# Sheet1.net
KiCad netlist of a schematic drawn in Altium Designer
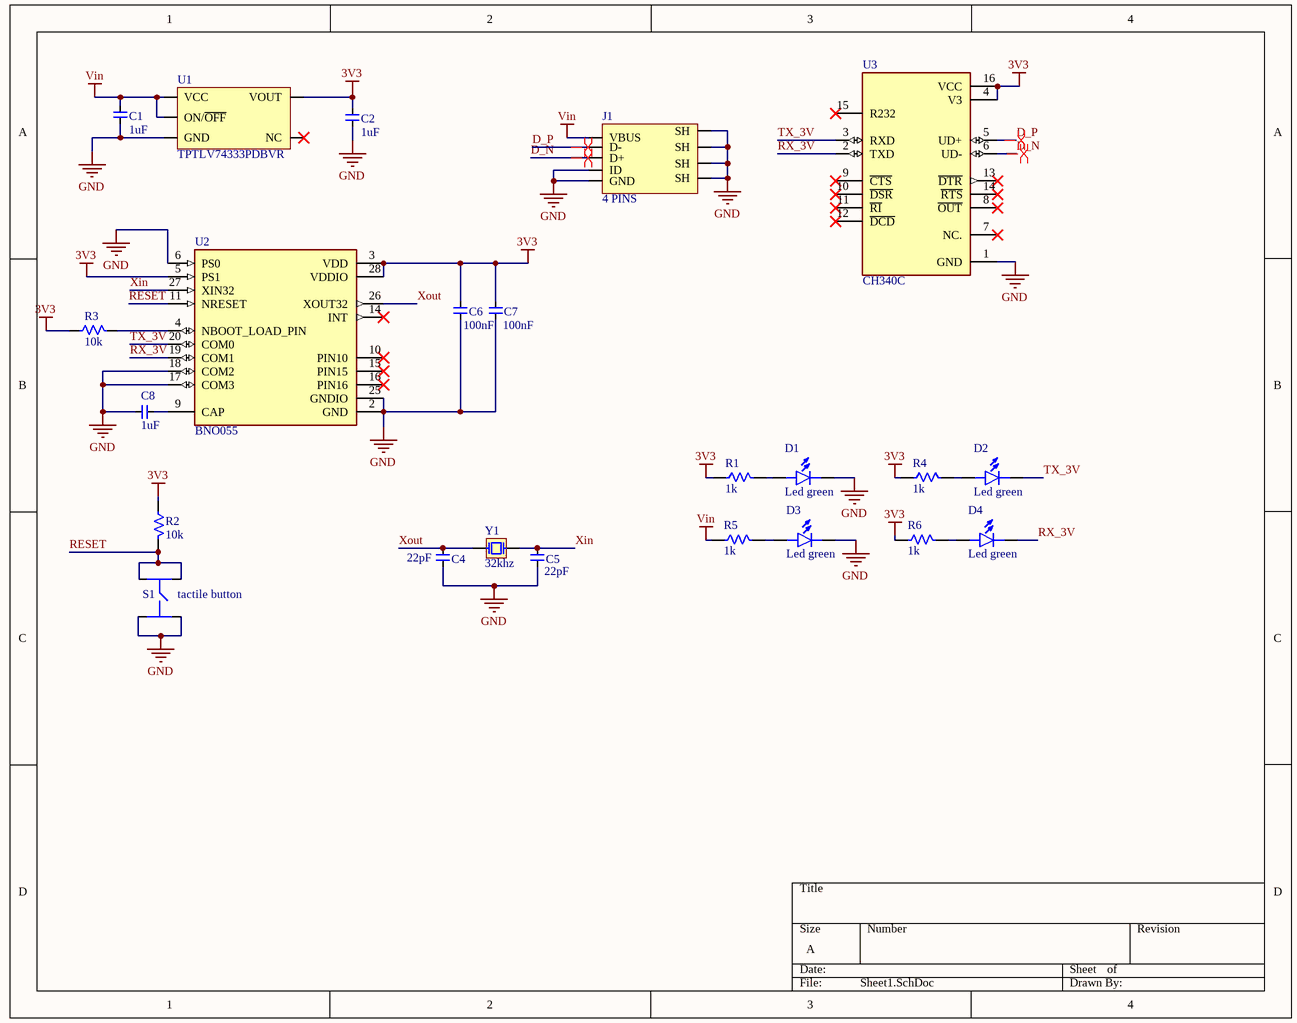
[diagram p0: Sheet1.SchDoc]

(export (version "E")
  (design (tool "Eeschema 10.0.6"))
  (components
    (comp (ref "C1")
      (value "1uF")
      (footprint "0603 cap")
      (description "25V 1uF X7R ±10% 0603 Multilayer Ceramic Capacitors MLCC - SMD/SMT ROHS")
      (fields
        (field (name "MANUFACTURER") "PSA(Prosperity Dielectrics)")
        (field (name "MFR. PART #") "FS18X105K250PBG")
      )
      (libsource (lib "Schlib1") (part "1uF"))
    )
    (comp (ref "C2")
      (value "1uF")
      (footprint "0603 cap")
      (description "25V 1uF X7R ±10% 0603 Multilayer Ceramic Capacitors MLCC - SMD/SMT ROHS")
      (fields
        (field (name "MANUFACTURER") "PSA(Prosperity Dielectrics)")
        (field (name "MFR. PART #") "FS18X105K250PBG")
      )
      (libsource (lib "Schlib1") (part "1uF"))
    )
    (comp (ref "C4")
      (value "22pF")
      (footprint "0603 cap")
      (description "50V 22pF C0G ±5% 0603 Multilayer Ceramic Capacitors MLCC - SMD/SMT ROHS")
      (fields
        (field (name "MANUFACTURER") "PSA(Prosperity Dielectrics)")
        (field (name "MFR. PART #") "FN18N220J500PSG")
      )
      (libsource (lib "Schlib1") (part "22pF capacitor"))
    )
    (comp (ref "C5")
      (value "22pF")
      (footprint "0603 cap")
      (description "50V 22pF C0G ±5% 0603 Multilayer Ceramic Capacitors MLCC - SMD/SMT ROHS")
      (fields
        (field (name "MANUFACTURER") "PSA(Prosperity Dielectrics)")
        (field (name "MFR. PART #") "FN18N220J500PSG")
      )
      (libsource (lib "Schlib1") (part "22pF capacitor"))
    )
    (comp (ref "C6")
      (value "100nF")
      (footprint "0603 cap")
      (description "50V 100nF X7R ±10% 0603 Multilayer Ceramic Capacitors MLCC - SMD/SMT ROHS")
      (fields
        (field (name "MANUFACTURER") "PSA(Prosperity Dielectrics)")
        (field (name "MFR. PART #") "FN18X104K500PBG")
      )
      (libsource (lib "Schlib1") (part "100nF capacitor"))
    )
    (comp (ref "C7")
      (value "100nF")
      (footprint "0603 cap")
      (description "50V 100nF X7R ±10% 0603 Multilayer Ceramic Capacitors MLCC - SMD/SMT ROHS")
      (fields
        (field (name "MANUFACTURER") "PSA(Prosperity Dielectrics)")
        (field (name "MFR. PART #") "FN18X104K500PBG")
      )
      (libsource (lib "Schlib1") (part "100nF capacitor"))
    )
    (comp (ref "C8")
      (value "1uF")
      (footprint "0603 cap")
      (description "25V 1uF X7R ±10% 0603 Multilayer Ceramic Capacitors MLCC - SMD/SMT ROHS")
      (fields
        (field (name "MANUFACTURER") "PSA(Prosperity Dielectrics)")
        (field (name "MFR. PART #") "FS18X105K250PBG")
      )
      (libsource (lib "Schlib1") (part "1uF"))
    )
    (comp (ref "D1")
      (value "Led green")
      (footprint "0805led")
      (description "Emerald 0805 Light Emitting Diodes (LED) ROHS")
      (fields (field (name "MANUFACTURER") "Yongyu Photoelectric") (field (name "MFR. PART #") "SZYY0805G"))
      (libsource (lib "Schlib1") (part "Led green"))
    )
    (comp (ref "D2")
      (value "Led green")
      (footprint "0805led")
      (description "Emerald 0805 Light Emitting Diodes (LED) ROHS")
      (fields (field (name "MANUFACTURER") "Yongyu Photoelectric") (field (name "MFR. PART #") "SZYY0805G"))
      (libsource (lib "Schlib1") (part "Led green"))
    )
    (comp (ref "D3")
      (value "Led green")
      (footprint "0805led")
      (description "Emerald 0805 Light Emitting Diodes (LED) ROHS")
      (fields (field (name "MANUFACTURER") "Yongyu Photoelectric") (field (name "MFR. PART #") "SZYY0805G"))
      (libsource (lib "Schlib1") (part "Led green"))
    )
    (comp (ref "D4")
      (value "Led green")
      (footprint "0805led")
      (description "Emerald 0805 Light Emitting Diodes (LED) ROHS")
      (fields (field (name "MANUFACTURER") "Yongyu Photoelectric") (field (name "MFR. PART #") "SZYY0805G"))
      (libsource (lib "Schlib1") (part "Led green"))
    )
    (comp (ref "J1")
      (value "4 PINS")
      (footprint "Micro USB")
      (description "1.8A USB 2.0 1 Horizontal attachment 5P Mother -20℃~+85℃ Micro-B SMD USB Connectors ROHS")
      (fields (field (name "MANUFACTURER") "SHOU HAN") (field (name "MFR. PART #") "MicroXNJ"))
      (libsource (lib "Schlib1") (part "Micro USB"))
    )
    (comp (ref "R1")
      (value "1k")
      (footprint "0603 res")
      (description "100mW Thick Film Resistors 75V ±100ppm/℃ ±1% 1kΩ 0603 Chip Resistor - Surface Mount ROHS")
      (fields
        (field (name "MANUFACTURER") "UNI-ROYAL(Uniroyal Elec)")
        (field (name "MFR. PART #") "0603WAF1001T5E")
      )
      (libsource (lib "Schlib1") (part "1k resistor"))
    )
    (comp (ref "R2")
      (value "10k")
      (footprint "0603 res")
      (description "100mW Thick Film Resistors 75V ±100ppm/℃ ±1% 10kΩ 0603 Chip Resistor - Surface Mount ROHS")
      (fields
        (field (name "MANUFACTURER") "UNI-ROYAL(Uniroyal Elec)")
        (field (name "MFR. PART #") "0603WAF1002T5E")
      )
      (libsource (lib "Schlib1") (part "10k resistor"))
    )
    (comp (ref "R3")
      (value "10k")
      (footprint "0603 res")
      (description "100mW Thick Film Resistors 75V ±100ppm/℃ ±1% 10kΩ 0603 Chip Resistor - Surface Mount ROHS")
      (fields
        (field (name "MANUFACTURER") "UNI-ROYAL(Uniroyal Elec)")
        (field (name "MFR. PART #") "0603WAF1002T5E")
      )
      (libsource (lib "Schlib1") (part "10k resistor"))
    )
    (comp (ref "R4")
      (value "1k")
      (footprint "0603 res")
      (description "100mW Thick Film Resistors 75V ±100ppm/℃ ±1% 1kΩ 0603 Chip Resistor - Surface Mount ROHS")
      (fields
        (field (name "MANUFACTURER") "UNI-ROYAL(Uniroyal Elec)")
        (field (name "MFR. PART #") "0603WAF1001T5E")
      )
      (libsource (lib "Schlib1") (part "1k resistor"))
    )
    (comp (ref "R5")
      (value "1k")
      (footprint "0603 res")
      (description "100mW Thick Film Resistors 75V ±100ppm/℃ ±1% 1kΩ 0603 Chip Resistor - Surface Mount ROHS")
      (fields
        (field (name "MANUFACTURER") "UNI-ROYAL(Uniroyal Elec)")
        (field (name "MFR. PART #") "0603WAF1001T5E")
      )
      (libsource (lib "Schlib1") (part "1k resistor"))
    )
    (comp (ref "R6")
      (value "1k")
      (footprint "0603 res")
      (description "100mW Thick Film Resistors 75V ±100ppm/℃ ±1% 1kΩ 0603 Chip Resistor - Surface Mount ROHS")
      (fields
        (field (name "MANUFACTURER") "UNI-ROYAL(Uniroyal Elec)")
        (field (name "MFR. PART #") "0603WAF1001T5E")
      )
      (libsource (lib "Schlib1") (part "1k resistor"))
    )
    (comp (ref "S1")
      (value "tactile button")
      (footprint "button")
      (fields
        (field (name "MANUFACTURER") "XKB Connection")
        (field (name "MFR. PART #") "UK-B0240-R-250")
        (field (name "LCSC PART #") "C318884")
      )
      (libsource (lib "Schlib1") (part "Button"))
    )
    (comp (ref "U1")
      (value "TPTLV74333PDBVR")
      (footprint "SOT-23")
      (fields (field (name "MANUFACTURER") "TECH PUBLIC") (field (name "LCSC PART #") "C3021096"))
      (libsource (lib "Schlib1") (part "TPTLV74333PDBVR"))
    )
    (comp (ref "U2")
      (value "BNO055")
      (footprint "LGA28R50P4X10_380X520X100")
      (description "LGA-28(3.8x5.2) Accelerometers ROHS")
      (fields (field (name "MANUFACTURER") "Bosch Sensortec") (field (name "LCSC PART #") "C93216"))
      (libsource (lib "Schlib1") (part "BNO055"))
    )
    (comp (ref "U3")
      (value "CH340C")
      (footprint "sop 16")
      (description "2Mbps Transceiver USB 2.0 SOP-16 USB ICs ROHS")
      (fields (field (name "MANUFACTURER") "WCH") (field (name "LCSC PART #") "C84681"))
      (libsource (lib "Schlib1") (part "CH340C"))
    )
    (comp (ref "Y1")
      (value "32khz")
      (footprint "XTAL_ABS06-107-32.768KHZ-T")
      (description "32.768kHz 6pF ±10ppm SMD2012-2P Crystals ROHS")
      (fields
        (field (name "MANUFACTURER") "Abracon LLC")
        (field (name "MFR. PART #") "ABS06-32.768KHZ-6-1-T")
      )
      (libsource (lib "Schlib1") (part "32khz"))
    )
  )
  (nets
    (net (code "1") (name "/D_N") (class "Default")
      (node (ref "J1") (pin "3") (pinfunction "D+_3") (pintype "passive"))
      (node (ref "U3") (pin "6") (pinfunction "UD-_6") (pintype "bidirectional"))
    )
    (net (code "2") (name "/D_P") (class "Default")
      (node (ref "J1") (pin "2") (pinfunction "D-_2") (pintype "passive"))
      (node (ref "U3") (pin "5") (pinfunction "UD+_5") (pintype "bidirectional"))
    )
    (net (code "3") (name "/RESET") (class "Default")
      (node (ref "R2") (pin "2") (pinfunction "2_2") (pintype "passive"))
      (node (ref "S1") (pin "C") (pinfunction "C_C") (pintype "passive"))
      (node (ref "S1") (pin "D") (pinfunction "D_D") (pintype "passive"))
      (node (ref "U2") (pin "11") (pinfunction "NRESET_11") (pintype "input"))
    )
    (net (code "4") (name "/RX_3V") (class "Default")
      (node (ref "D4") (pin "2") (pinfunction "2_2") (pintype "passive"))
      (node (ref "U2") (pin "19") (pinfunction "COM1_19") (pintype "bidirectional"))
      (node (ref "U3") (pin "2") (pinfunction "TXD_2") (pintype "bidirectional"))
    )
    (net (code "5") (name "/TX_3V") (class "Default")
      (node (ref "D2") (pin "2") (pinfunction "2_2") (pintype "passive"))
      (node (ref "U2") (pin "20") (pinfunction "COM0_20") (pintype "bidirectional"))
      (node (ref "U3") (pin "3") (pinfunction "RXD_3") (pintype "bidirectional"))
    )
    (net (code "6") (name "/Xin") (class "Default")
      (node (ref "C5") (pin "2") (pinfunction "2_2") (pintype "passive"))
      (node (ref "U2") (pin "27") (pinfunction "XIN32_27") (pintype "input"))
      (node (ref "Y1") (pin "2") (pinfunction "2_2") (pintype "passive"))
    )
    (net (code "7") (name "/Xout") (class "Default")
      (node (ref "C4") (pin "2") (pinfunction "2_2") (pintype "passive"))
      (node (ref "U2") (pin "26") (pinfunction "XOUT32_26") (pintype "output"))
      (node (ref "Y1") (pin "1") (pinfunction "1_1") (pintype "passive"))
    )
    (net (code "8") (name "3V3") (class "Default")
      (node (ref "C2") (pin "2") (pinfunction "2_2") (pintype "passive"))
      (node (ref "C6") (pin "2") (pinfunction "2_2") (pintype "passive"))
      (node (ref "C7") (pin "2") (pinfunction "2_2") (pintype "passive"))
      (node (ref "R1") (pin "1") (pinfunction "1_1") (pintype "passive"))
      (node (ref "R2") (pin "1") (pinfunction "1_1") (pintype "passive"))
      (node (ref "R3") (pin "1") (pinfunction "1_1") (pintype "passive"))
      (node (ref "R4") (pin "1") (pinfunction "1_1") (pintype "passive"))
      (node (ref "R6") (pin "1") (pinfunction "1_1") (pintype "passive"))
      (node (ref "U1") (pin "5") (pinfunction "VOUT_5") (pintype "passive"))
      (node (ref "U2") (pin "28") (pinfunction "VDDIO_28") (pintype "power_in"))
      (node (ref "U2") (pin "3") (pinfunction "VDD_3") (pintype "power_in"))
      (node (ref "U2") (pin "5") (pinfunction "PS1_5") (pintype "input"))
      (node (ref "U3") (pin "16") (pinfunction "VCC_16") (pintype "power_in"))
      (node (ref "U3") (pin "4") (pinfunction "V3_4") (pintype "power_in"))
    )
    (net (code "9") (name "GND") (class "Default")
      (node (ref "C1") (pin "1") (pinfunction "1_1") (pintype "passive"))
      (node (ref "C2") (pin "1") (pinfunction "1_1") (pintype "passive"))
      (node (ref "C4") (pin "1") (pinfunction "1_1") (pintype "passive"))
      (node (ref "C5") (pin "1") (pinfunction "1_1") (pintype "passive"))
      (node (ref "C6") (pin "1") (pinfunction "1_1") (pintype "passive"))
      (node (ref "C7") (pin "1") (pinfunction "1_1") (pintype "passive"))
      (node (ref "C8") (pin "2") (pinfunction "2_2") (pintype "passive"))
      (node (ref "D1") (pin "2") (pinfunction "2_2") (pintype "passive"))
      (node (ref "D3") (pin "2") (pinfunction "2_2") (pintype "passive"))
      (node (ref "J1") (pin "4") (pinfunction "ID_4") (pintype "passive"))
      (node (ref "J1") (pin "5") (pinfunction "GND_5") (pintype "passive"))
      (node (ref "J1") (pin "6") (pinfunction "SH_6") (pintype "passive"))
      (node (ref "J1") (pin "7") (pinfunction "SH_7") (pintype "passive"))
      (node (ref "J1") (pin "8") (pinfunction "SH_8") (pintype "passive"))
      (node (ref "J1") (pin "9") (pinfunction "SH_9") (pintype "passive"))
      (node (ref "S1") (pin "A") (pinfunction "A_A") (pintype "passive"))
      (node (ref "S1") (pin "B") (pinfunction "B_B") (pintype "passive"))
      (node (ref "U1") (pin "2") (pinfunction "GND_2") (pintype "passive"))
      (node (ref "U2") (pin "17") (pinfunction "COM3_17") (pintype "bidirectional"))
      (node (ref "U2") (pin "18") (pinfunction "COM2_18") (pintype "bidirectional"))
      (node (ref "U2") (pin "2") (pinfunction "GND_2") (pintype "power_in"))
      (node (ref "U2") (pin "25") (pinfunction "GNDIO_25") (pintype "power_in"))
      (node (ref "U2") (pin "6") (pinfunction "PS0_6") (pintype "input"))
      (node (ref "U3") (pin "1") (pinfunction "GND_1") (pintype "power_in"))
    )
    (net (code "10") (name "Net-(D1-Pad1)") (class "Default")
      (node (ref "D1") (pin "1") (pinfunction "1_1") (pintype "passive"))
      (node (ref "R1") (pin "2") (pinfunction "2_2") (pintype "passive"))
    )
    (net (code "11") (name "Net-(D2-Pad1)") (class "Default")
      (node (ref "D2") (pin "1") (pinfunction "1_1") (pintype "passive"))
      (node (ref "R4") (pin "2") (pinfunction "2_2") (pintype "passive"))
    )
    (net (code "12") (name "Net-(D3-Pad1)") (class "Default")
      (node (ref "D3") (pin "1") (pinfunction "1_1") (pintype "passive"))
      (node (ref "R5") (pin "2") (pinfunction "2_2") (pintype "passive"))
    )
    (net (code "13") (name "Net-(D4-Pad1)") (class "Default")
      (node (ref "D4") (pin "1") (pinfunction "1_1") (pintype "passive"))
      (node (ref "R6") (pin "2") (pinfunction "2_2") (pintype "passive"))
    )
    (net (code "14") (name "Net-(U2-CAP)") (class "Default")
      (node (ref "C8") (pin "1") (pinfunction "1_1") (pintype "passive"))
      (node (ref "U2") (pin "9") (pinfunction "CAP_9") (pintype "passive"))
    )
    (net (code "15") (name "Net-(U2-NBOOT_LOAD_PIN)") (class "Default")
      (node (ref "R3") (pin "2") (pinfunction "2_2") (pintype "passive"))
      (node (ref "U2") (pin "4") (pinfunction "NBOOT_LOAD_PIN_4") (pintype "bidirectional"))
    )
    (net (code "16") (name "Vin") (class "Default")
      (node (ref "C1") (pin "2") (pinfunction "2_2") (pintype "passive"))
      (node (ref "J1") (pin "1") (pinfunction "VBUS_1") (pintype "passive"))
      (node (ref "R5") (pin "1") (pinfunction "1_1") (pintype "passive"))
      (node (ref "U1") (pin "1") (pinfunction "VCC_1") (pintype "passive"))
      (node (ref "U1") (pin "3") (pinfunction "ON/~{OFF}_3") (pintype "passive"))
    )
    (net (code "17") (name "unconnected-(U1-NC-Pad4)") (class "Default")
      (node (ref "U1") (pin "4") (pinfunction "NC_4") (pintype "passive+no_connect"))
    )
    (net (code "18") (name "unconnected-(U2-INT-Pad14)") (class "Default")
      (node (ref "U2") (pin "14") (pinfunction "INT_14") (pintype "output+no_connect"))
    )
    (net (code "19") (name "unconnected-(U2-PIN10-Pad10)") (class "Default")
      (node (ref "U2") (pin "10") (pinfunction "PIN10_10") (pintype "power_in+no_connect"))
    )
    (net (code "20") (name "unconnected-(U2-PIN15-Pad15)") (class "Default")
      (node (ref "U2") (pin "15") (pinfunction "PIN15_15") (pintype "power_in+no_connect"))
    )
    (net (code "21") (name "unconnected-(U2-PIN16-Pad16)") (class "Default")
      (node (ref "U2") (pin "16") (pinfunction "PIN16_16") (pintype "power_in+no_connect"))
    )
    (net (code "22") (name "unconnected-(U3-NC.-Pad7)") (class "Default")
      (node (ref "U3") (pin "7") (pinfunction "NC._7") (pintype "passive+no_connect"))
    )
    (net (code "23") (name "unconnected-(U3-R232-Pad15)") (class "Default")
      (node (ref "U3") (pin "15") (pinfunction "R232_15") (pintype "passive+no_connect"))
    )
    (net (code "24") (name "unconnected-(U3-~{CTS}-Pad9)") (class "Default")
      (node (ref "U3") (pin "9") (pinfunction "~{CTS}_9") (pintype "passive+no_connect"))
    )
    (net (code "25") (name "unconnected-(U3-~{DCD}-Pad12)") (class "Default")
      (node (ref "U3") (pin "12") (pinfunction "~{DCD}_12") (pintype "passive+no_connect"))
    )
    (net (code "26") (name "unconnected-(U3-~{DSR}-Pad10)") (class "Default")
      (node (ref "U3") (pin "10") (pinfunction "~{DSR}_10") (pintype "passive+no_connect"))
    )
    (net (code "27") (name "unconnected-(U3-~{DTR}-Pad13)") (class "Default")
      (node (ref "U3") (pin "13") (pinfunction "~{DTR}_13") (pintype "output+no_connect"))
    )
    (net (code "28") (name "unconnected-(U3-~{OUT}-Pad8)") (class "Default")
      (node (ref "U3") (pin "8") (pinfunction "~{OUT}_8") (pintype "passive+no_connect"))
    )
    (net (code "29") (name "unconnected-(U3-~{RI}-Pad11)") (class "Default")
      (node (ref "U3") (pin "11") (pinfunction "~{RI}_11") (pintype "passive+no_connect"))
    )
    (net (code "30") (name "unconnected-(U3-~{RTS}-Pad14)") (class "Default")
      (node (ref "U3") (pin "14") (pinfunction "~{RTS}_14") (pintype "passive+no_connect"))
    )
  )
)
